# 20_-_SERVO.net
KiCad netlist of a schematic drawn in Altium Designer
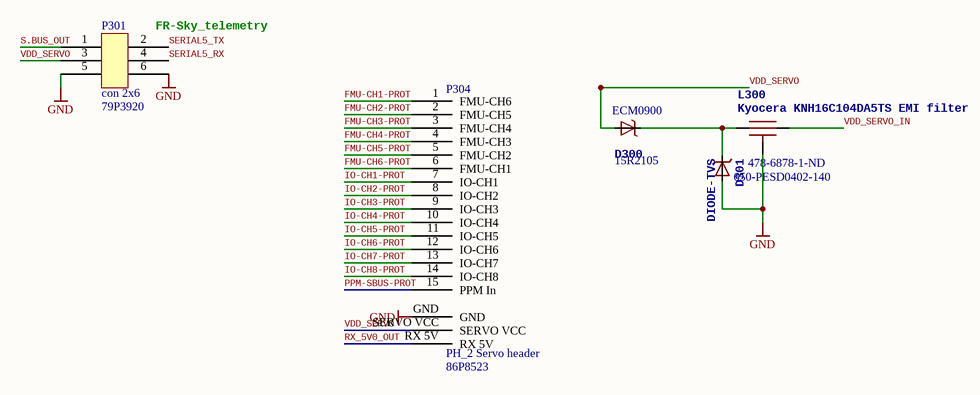
[diagram p0: [20] - SERVO.SchDoc]

(export (version "E")
  (design (tool "Eeschema 10.0.6"))
  (components
    (comp (ref "D300")
      (value "MSS1P4-M3")
      (footprint "MICROSMP")
      (description "Diode, Schottky, 40V, 1A, MicroSMP, SMD")
      (fields (field (name "SUPPLIER PART NUMBER 1") "15R2105") (field (name "3DR_PARTNO") "ECM0900"))
      (libsource (lib "PCA_0005_FULL_CB_REV_A") (part "DIODE-SCHOTTKY_MSMP"))
    )
    (comp (ref "D301")
      (value "DIODE-TVS")
      (footprint "0402-TVS")
      (description "Diode, TVS, 14VWM, 40VC, 0402, SMD")
      (fields
        (field (name "SUPPLIER PART NUMBER 1") "650-PESD0402-140")
        (field (name "3DR_PARTNO") "ECM0837")
      )
      (libsource (lib "PCA_0005_FULL_CB_REV_A") (part "DIODE-TVS"))
    )
    (comp (ref "L300")
      (value "Kyocera KNH16C104DA5TS EMI filter")
      (footprint "KYOCERA-KNH16-DA")
      (description "Capacitor, Filter, 0.1uF, 25V, 2A, 0603, SMD")
      (fields (field (name "SUPPLIER PART NUMBER 1") "478-6878-1-ND") (field (name "3DR_PARTNO") "ECM0719"))
      (libsource (lib "PCA_0005_FULL_CB_REV_A") (part "KNH16C104DA5TS"))
    )
    (comp (ref "P301")
      (value "con 2x6")
      (footprint "TSW-103-07-G-D")
      (description "Connector, Header, 6Pos, 2.54MM, Vert, THT, Au")
      (fields (field (name "SUPPLIER PART NUMBER 1") "79P3920") (field (name "3DR_PARTNO") "PRT0445"))
      (libsource (lib "PCA_0005_FULL_CB_REV_A") (part "con 2x6"))
    )
    (comp (ref "P304")
      (value "PH_2 Servo header")
      (footprint "TSW-115-08-G-T-RA")
      (description "Connector, Header, 45Pos, 2.54MM, R/A, THT, Tin")
      (fields (field (name "SUPPLIER PART NUMBER 1") "86P8523") (field (name "3DR_PARTNO") "PRT0446"))
      (libsource (lib "PCA_0005_FULL_CB_REV_A") (part "PH_2 Servo header"))
    )
  )
  (nets
    (net (code "1") (name "/FMU-CH1-PROT") (class "Default")
      (node (ref "P304") (pin "1") (pinfunction "FMU-CH6_1") (pintype "passive"))
    )
    (net (code "2") (name "/FMU-CH2-PROT") (class "Default")
      (node (ref "P304") (pin "2") (pinfunction "FMU-CH5_2") (pintype "passive"))
    )
    (net (code "3") (name "/FMU-CH3-PROT") (class "Default")
      (node (ref "P304") (pin "3") (pinfunction "FMU-CH4_3") (pintype "passive"))
    )
    (net (code "4") (name "/FMU-CH4-PROT") (class "Default")
      (node (ref "P304") (pin "4") (pinfunction "FMU-CH3_4") (pintype "passive"))
    )
    (net (code "5") (name "/FMU-CH5-PROT") (class "Default")
      (node (ref "P304") (pin "5") (pinfunction "FMU-CH2_5") (pintype "passive"))
    )
    (net (code "6") (name "/FMU-CH6-PROT") (class "Default")
      (node (ref "P304") (pin "6") (pinfunction "FMU-CH1_6") (pintype "passive"))
    )
    (net (code "7") (name "/IO-CH1-PROT") (class "Default")
      (node (ref "P304") (pin "7") (pinfunction "IO-CH1_7") (pintype "passive"))
    )
    (net (code "8") (name "/IO-CH2-PROT") (class "Default")
      (node (ref "P304") (pin "8") (pinfunction "IO-CH2_8") (pintype "passive"))
    )
    (net (code "9") (name "/IO-CH3-PROT") (class "Default")
      (node (ref "P304") (pin "9") (pinfunction "IO-CH3_9") (pintype "passive"))
    )
    (net (code "10") (name "/IO-CH4-PROT") (class "Default")
      (node (ref "P304") (pin "10") (pinfunction "IO-CH4_10") (pintype "passive"))
    )
    (net (code "11") (name "/IO-CH5-PROT") (class "Default")
      (node (ref "P304") (pin "11") (pinfunction "IO-CH5_11") (pintype "passive"))
    )
    (net (code "12") (name "/IO-CH6-PROT") (class "Default")
      (node (ref "P304") (pin "12") (pinfunction "IO-CH6_12") (pintype "passive"))
    )
    (net (code "13") (name "/IO-CH7-PROT") (class "Default")
      (node (ref "P304") (pin "13") (pinfunction "IO-CH7_13") (pintype "passive"))
    )
    (net (code "14") (name "/IO-CH8-PROT") (class "Default")
      (node (ref "P304") (pin "14") (pinfunction "IO-CH8_14") (pintype "passive"))
    )
    (net (code "15") (name "/PPM-SBUS-PROT") (class "Default")
      (node (ref "P304") (pin "15") (pinfunction "PPM_In_15") (pintype "passive"))
    )
    (net (code "16") (name "/RX_5V0_OUT") (class "Default")
      (node (ref "P304") (pin "RX_5V") (pinfunction "RX_5V_RX_5V") (pintype "passive"))
    )
    (net (code "17") (name "/S.BUS_OUT") (class "Default")
      (node (ref "P301") (pin "1") (pinfunction "1_1") (pintype "passive"))
    )
    (net (code "18") (name "/SERIAL5_RX") (class "Default")
      (node (ref "P301") (pin "4") (pinfunction "4_4") (pintype "passive"))
    )
    (net (code "19") (name "/SERIAL5_TX") (class "Default")
      (node (ref "P301") (pin "2") (pinfunction "2_2") (pintype "passive"))
    )
    (net (code "20") (name "/VDD_SERVO") (class "Default")
      (node (ref "D300") (pin "ANODE") (pinfunction "A_ANODE") (pintype "passive"))
      (node (ref "P301") (pin "3") (pinfunction "3_3") (pintype "passive"))
      (node (ref "P304") (pin "SERVO_VCC") (pinfunction "SERVO_VCC_SERVO_VCC") (pintype "passive"))
    )
    (net (code "21") (name "/VDD_SERVO_IN") (class "Default")
      (node (ref "L300") (pin "P$2") (pinfunction "P$2_P$2") (pintype "passive"))
    )
    (net (code "22") (name "GND") (class "Default")
      (node (ref "D301") (pin "A") (pinfunction "A_A") (pintype "passive"))
      (node (ref "L300") (pin "GND") (pinfunction "GND_GND") (pintype "passive"))
      (node (ref "P301") (pin "5") (pinfunction "5_5") (pintype "passive"))
      (node (ref "P301") (pin "6") (pinfunction "6_6") (pintype "passive"))
      (node (ref "P304") (pin "GND") (pinfunction "GND_GND") (pintype "passive"))
    )
    (net (code "23") (name "Net-(D300-C)") (class "Default")
      (node (ref "D300") (pin "CATHODE") (pinfunction "C_CATHODE") (pintype "passive"))
      (node (ref "D301") (pin "C") (pinfunction "C_C") (pintype "passive"))
      (node (ref "L300") (pin "P$1") (pinfunction "P$1_P$1") (pintype "passive"))
    )
  )
)
